# CPU-board-Sheet1-multi-rev_0_1.net
KiCad netlist of a schematic drawn in Altium Designer
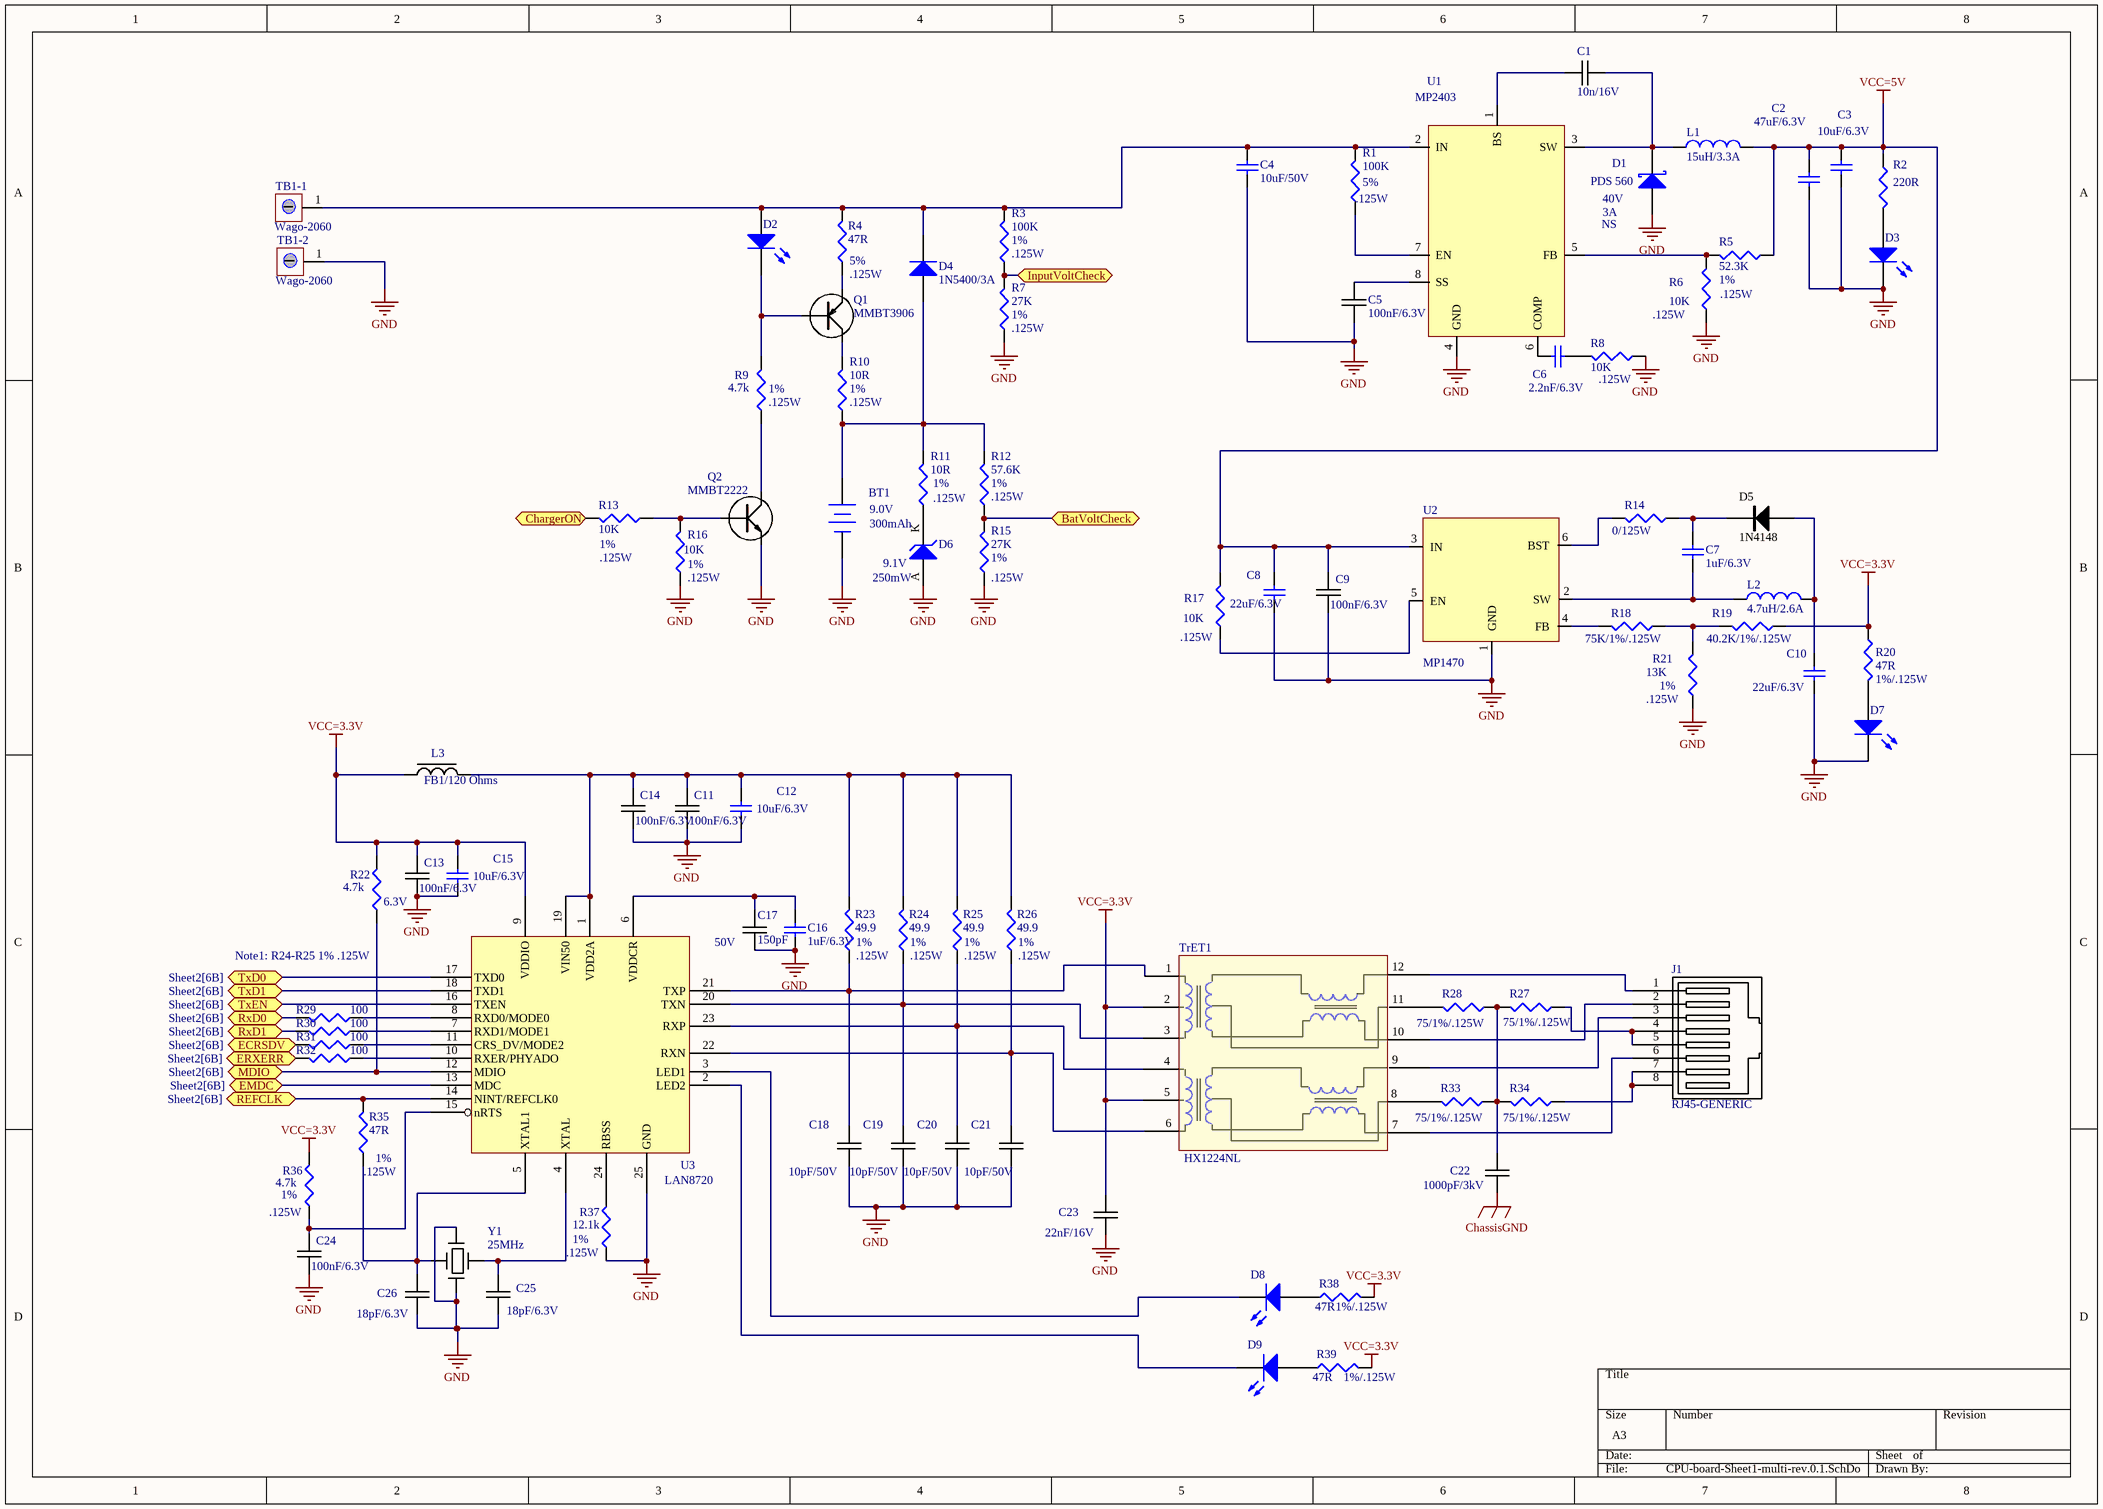
[diagram p0: CPU-board-Sheet1-multi-rev.0.1.SchDoc]

(export (version "E")
  (design (tool "Eeschema 10.0.6"))
  (components
    (comp (ref "BT1")
      (value "9.0V")
      (footprint "BAT-2")
      (description "Multicell Battery")
      (fields
        (field (name "MANUFACTURER") "Guangdong, China (Mainland)")
        (field (name "PUBLISHER") "sunbangpower.en.alibaba.com")
      )
      (libsource (lib "Miscellaneous Devices") (part "Battery"))
    )
    (comp (ref "C1")
      (value "10n/16V")
      (footprint "0402C-GENERIC")
      (description "CAPACITOR 0805 CERAMIC")
      (fields (field (name "MANUFACTURER") "Murata Electronics"))
      (libsource (lib "vh_altium_library") (part "0805C-18PF-50V-C0G-JOH"))
    )
    (comp (ref "C2")
      (value "47uF/6.3V")
      (footprint "1210C-GENERIC")
      (description "Capacitor")
      (fields (field (name "MANUFACTURER") "Murata") (field (name "PUBLISHER") "Altium Limited"))
      (libsource (lib "Miscellaneous Devices") (part "Cap"))
    )
    (comp (ref "C3")
      (value "10uF/6.3V")
      (footprint "0402C-GENERIC")
      (description "Capacitor")
      (fields (field (name "MANUFACTURER") "Murata") (field (name "PUBLISHER") "Altium Limited"))
      (libsource (lib "Miscellaneous Devices") (part "Cap"))
    )
    (comp (ref "C4")
      (value "10uF/50V")
      (footprint "1206C-GENERIC")
      (description "Capacitor")
      (fields (field (name "MANUFACTURER") "Murata") (field (name "PUBLISHER") "Altium Limited"))
      (libsource (lib "Miscellaneous Devices") (part "Cap"))
    )
    (comp (ref "C5")
      (value "100nF/6.3V")
      (footprint "0402C-GENERIC")
      (description "CAPACITOR 0805 CERAMIC")
      (fields (field (name "MANUFACTURER") "Taiyo Yuden"))
      (libsource (lib "vh_altium_library") (part "0805C-18PF-50V-C0G-JOH"))
    )
    (comp (ref "C6")
      (value "2.2nF/6.3V")
      (footprint "0402C-GENERIC")
      (description "Capacitor")
      (fields (field (name "MANUFACTURER") "Murata") (field (name "PUBLISHER") "Altium Limited"))
      (libsource (lib "Miscellaneous Devices") (part "Cap"))
    )
    (comp (ref "C7")
      (value "1uF/6.3V")
      (footprint "0402C-GENERIC")
      (description "Capacitor")
      (fields (field (name "MANUFACTURER") "Murata") (field (name "PUBLISHER") "Altium Limited"))
      (libsource (lib "Miscellaneous Devices") (part "Cap"))
    )
    (comp (ref "C8")
      (value "22uF/6.3V")
      (footprint "1206C-GENERIC")
      (description "Capacitor")
      (fields (field (name "MANUFACTURER") "Murata") (field (name "PUBLISHER") "Altium Limited"))
      (libsource (lib "Miscellaneous Devices") (part "Cap"))
    )
    (comp (ref "C9")
      (value "100nF/6.3V")
      (footprint "0402C-GENERIC")
      (description "CAPACITOR 0805 CERAMIC")
      (fields (field (name "MANUFACTURER") "Taiyo Yuden"))
      (libsource (lib "vh_altium_library") (part "0805C-18PF-50V-C0G-JOH"))
    )
    (comp (ref "C10")
      (value "22uF/6.3V")
      (footprint "1206C-GENERIC")
      (description "Capacitor")
      (fields (field (name "MANUFACTURER") "Murata") (field (name "PUBLISHER") "Altium Limited"))
      (libsource (lib "Miscellaneous Devices") (part "Cap"))
    )
    (comp (ref "C11")
      (value "100nF/6.3V")
      (footprint "0402C-GENERIC")
      (description "CAPACITOR 0805 CERAMIC")
      (fields (field (name "MANUFACTURER") "Taiyo Yuden"))
      (libsource (lib "vh_altium_library") (part "0805C-18PF-50V-C0G-JOH"))
    )
    (comp (ref "C12")
      (value "10uF/6.3V")
      (footprint "0402C-GENERIC")
      (description "Capacitor")
      (fields (field (name "MANUFACTURER") "Murata") (field (name "PUBLISHER") "Altium Limited"))
      (libsource (lib "Miscellaneous Devices") (part "Cap"))
    )
    (comp (ref "C13")
      (value "100nF/6.3V")
      (footprint "0402C-GENERIC")
      (description "CAPACITOR 0805 CERAMIC")
      (fields (field (name "MANUFACTURER") "Taiyo Yuden"))
      (libsource (lib "vh_altium_library") (part "0805C-18PF-50V-C0G-JOH"))
    )
    (comp (ref "C14")
      (value "100nF/6.3V")
      (footprint "0402C-GENERIC")
      (description "CAPACITOR 0805 CERAMIC")
      (fields (field (name "MANUFACTURER") "Taiyo Yuden"))
      (libsource (lib "vh_altium_library") (part "0805C-18PF-50V-C0G-JOH"))
    )
    (comp (ref "C15")
      (value "10uF/6.3V")
      (footprint "0402C-GENERIC")
      (description "Capacitor")
      (fields (field (name "MANUFACTURER") "Murata") (field (name "PUBLISHER") "Altium Limited"))
      (libsource (lib "Miscellaneous Devices") (part "Cap"))
    )
    (comp (ref "C16")
      (value "1uF/6.3V")
      (footprint "0402C-GENERIC")
      (description "Capacitor")
      (fields (field (name "MANUFACTURER") "Murata") (field (name "PUBLISHER") "Altium Limited"))
      (libsource (lib "Miscellaneous Devices") (part "Cap"))
    )
    (comp (ref "C17")
      (value "150pF")
      (footprint "0402C-GENERIC")
      (description "CAPACITOR 0805 CERAMIC")
      (fields (field (name "MANUFACTURER") "Wurth Electronics"))
      (libsource (lib "vh_altium_library") (part "0805C-18PF-50V-C0G-JOH"))
    )
    (comp (ref "C18")
      (value "10pF/50V")
      (footprint "0402C-GENERIC")
      (description "CAPACITOR 0805 CERAMIC")
      (fields (field (name "MANUFACTURER") "Murata"))
      (libsource (lib "vh_altium_library") (part "0805C-18PF-50V-C0G-JOH"))
    )
    (comp (ref "C19")
      (value "10pF/50V")
      (footprint "0402C-GENERIC")
      (description "CAPACITOR 0805 CERAMIC")
      (fields (field (name "MANUFACTURER") "Murata"))
      (libsource (lib "vh_altium_library") (part "0805C-18PF-50V-C0G-JOH"))
    )
    (comp (ref "C20")
      (value "10pF/50V")
      (footprint "0402C-GENERIC")
      (description "CAPACITOR 0805 CERAMIC")
      (fields (field (name "MANUFACTURER") "Murata"))
      (libsource (lib "vh_altium_library") (part "0805C-18PF-50V-C0G-JOH"))
    )
    (comp (ref "C21")
      (value "10pF/50V")
      (footprint "0402C-GENERIC")
      (description "CAPACITOR 0805 CERAMIC")
      (fields (field (name "MANUFACTURER") "Murata"))
      (libsource (lib "vh_altium_library") (part "0805C-18PF-50V-C0G-JOH"))
    )
    (comp (ref "C22")
      (value "1000pF/3kV")
      (footprint "1808")
      (description "CAPACITOR 1808CERAMIC")
      (fields (field (name "MANUFACTURER") "Johanson Dielctrics Inc"))
      (libsource (lib "vh_altium_library") (part "0805C-18PF-50V-C0G-JOH"))
    )
    (comp (ref "C23")
      (value "22nF/16V")
      (footprint "0402C-GENERIC")
      (description "CAPACITOR 0805 CERAMIC")
      (fields (field (name "MANUFACTURER") "Murata Electronics"))
      (libsource (lib "vh_altium_library") (part "0805C-18PF-50V-C0G-JOH"))
    )
    (comp (ref "C24")
      (value "100nF/6.3V")
      (footprint "0402C-GENERIC")
      (description "CAPACITOR 0805 CERAMIC")
      (fields (field (name "MANUFACTURER") "Taiyo Yuden"))
      (libsource (lib "vh_altium_library") (part "0805C-18PF-50V-C0G-JOH"))
    )
    (comp (ref "C25")
      (value "18pF/6.3V")
      (footprint "0402C-GENERIC")
      (description "CAPACITOR 0805 CERAMIC")
      (fields (field (name "MANUFACTURER") "Murata"))
      (libsource (lib "vh_altium_library") (part "0805C-18PF-50V-C0G-JOH"))
    )
    (comp (ref "C26")
      (value "18pF/6.3V")
      (footprint "0402C-GENERIC")
      (description "CAPACITOR 0805 CERAMIC")
      (fields (field (name "MANUFACTURER") "Murata"))
      (libsource (lib "vh_altium_library") (part "0805C-18PF-50V-C0G-JOH"))
    )
    (comp (ref "D1")
      (value "PDS 560")
      (footprint "SMB")
      (description "Schottky Diode")
      (fields (field (name "MANUFACTURER") "Diodes Incorporated") (field (name "PUBLISHER") "Altium Limited"))
      (libsource (lib "Miscellaneous Devices") (part "D Schottky"))
    )
    (comp (ref "D2")
      (value "LED2")
      (footprint "LED-SM")
      (description "Typical RED, GREEN, YELLOW, AMBER GaAs LED")
      (fields (field (name "MANUFACTURER") "Lite-On Inc") (field (name "PUBLISHER") "Altium Limited"))
      (libsource (lib "Miscellaneous Devices") (part "LED2"))
    )
    (comp (ref "D3")
      (value "LED2")
      (footprint "LED-SM")
      (description "Typical RED, GREEN, YELLOW, AMBER GaAs LED")
      (fields (field (name "MANUFACTURER") "Lite-On Inc") (field (name "PUBLISHER") "Altium Limited"))
      (libsource (lib "Miscellaneous Devices") (part "LED2"))
    )
    (comp (ref "D4")
      (value "1N5400/3A")
      (footprint "DO-41")
      (description "1 Amp General Purpose Rectifier")
      (fields (field (name "MANUFACTURER") "NTE Electronics") (field (name "PUBLISHER") "Altium Limited"))
      (libsource (lib "Miscellaneous Devices") (part "Diode 1N4007"))
    )
    (comp (ref "D5")
      (value "1N4148")
      (footprint "SOD-123")
      (description "1N4001")
      (fields (field (name "MANUFACTURER") "Vishay"))
      (libsource (lib "vh_altium_library") (part "1N4001"))
    )
    (comp (ref "D6")
      (value "9.1V")
      (footprint "SOT23-DIODE")
      (description "Zener Diode")
      (fields (field (name "MANUFACTURER") "NXP Semi") (field (name "PUBLISHER") "Altium Limited"))
      (libsource (lib "Miscellaneous Devices") (part "D Zener"))
    )
    (comp (ref "D7")
      (value "LED2")
      (footprint "LED-SM")
      (description "Typical RED, GREEN, YELLOW, AMBER GaAs LED")
      (fields (field (name "MANUFACTURER") "Lite-On Inc") (field (name "PUBLISHER") "Altium Limited"))
      (libsource (lib "Miscellaneous Devices") (part "LED2"))
    )
    (comp (ref "D8")
      (value "LED2")
      (footprint "LED-SM")
      (description "Typical RED, GREEN, YELLOW, AMBER GaAs LED")
      (fields (field (name "MANUFACTURER") "Lite-On Inc") (field (name "PUBLISHER") "Altium Limited"))
      (libsource (lib "Miscellaneous Devices") (part "LED2"))
    )
    (comp (ref "D9")
      (value "LED2")
      (footprint "LED-SM")
      (description "Typical RED, GREEN, YELLOW, AMBER GaAs LED")
      (fields (field (name "MANUFACTURER") "Lite-On Inc") (field (name "PUBLISHER") "Altium Limited"))
      (libsource (lib "Miscellaneous Devices") (part "LED2"))
    )
    (comp (ref "J1")
      (value "RJ45-GENERIC")
      (footprint "RJ45-8/8")
      (description "GENERIC RJ45 CONNECTOR 8 PIN")
      (fields (field (name "MANUFACTURER") "Assman WSW Components"))
      (libsource (lib "vh_altium_library") (part "RJ45-GENERIC"))
    )
    (comp (ref "L1")
      (value "15uH/3.3A")
      (footprint "Murata 15uH inductor")
      (description "Inductor")
      (fields (field (name "MANUFACTURER") "Murata") (field (name "PUBLISHER") "Altium Limited"))
      (libsource (lib "Miscellaneous Devices") (part "Inductor"))
    )
    (comp (ref "L2")
      (value "4.7uH/2.6A")
      (footprint "Inductor 4.7/6.8")
      (description "Inductor")
      (fields (field (name "MANUFACTURER") "Bourns") (field (name "PUBLISHER") "Altium Limited"))
      (libsource (lib "Miscellaneous Devices") (part "Inductor"))
    )
    (comp (ref "L3")
      (value "FB1/120 Ohms")
      (footprint "0603C-2U2")
      (description "1239AS-H-1R0N")
      (fields (field (name "MANUFACTURER") "Murata Electronics"))
      (libsource (lib "SMD Magnetics-SM") (part "1U-1239AS-TOKO"))
    )
    (comp (ref "Q1")
      (value "MMBT3906")
      (footprint "SOT23-BCE")
      (description "GENERIC PNP BIPOLAR TRANSISTOR")
      (fields (field (name "MANUFACTURER") "On Semi"))
      (libsource (lib "generic") (part "PNP-GENERIC"))
    )
    (comp (ref "Q2")
      (value "MMBT2222")
      (footprint "MMBT2222")
      (description "BC847 SMALL SIGNAL NPN TRANSISTOR")
      (fields (field (name "MANUFACTURER") "Diodes  Inc."))
      (libsource (lib "vh_altium_library") (part "MMBT2222"))
    )
    (comp (ref "R1")
      (value "100K")
      (footprint "0402R-TBD")
      (description "Resistor")
      (fields (field (name "MANUFACTURER") "Panasonic") (field (name "PUBLISHER") "Altium Limited"))
      (libsource (lib "Miscellaneous Devices") (part "Res3"))
    )
    (comp (ref "R2")
      (value "220R")
      (footprint "0402R-TBD")
      (description "Resistor")
      (fields (field (name "MANUFACTURER") "Panasonic") (field (name "PUBLISHER") "Altium Limited"))
      (libsource (lib "Miscellaneous Devices") (part "Res3"))
    )
    (comp (ref "R3")
      (value "100K")
      (footprint "0402R-TBD")
      (description "Resistor")
      (fields (field (name "MANUFACTURER") "Panasonic") (field (name "PUBLISHER") "Altium Limited"))
      (libsource (lib "Miscellaneous Devices") (part "Res3"))
    )
    (comp (ref "R4")
      (value "47R")
      (footprint "0402R-TBD")
      (description "Resistor")
      (fields (field (name "PUBLISHER") "Altium Limited"))
      (libsource (lib "Miscellaneous Devices") (part "Res3"))
    )
    (comp (ref "R5")
      (value "52.3K")
      (footprint "0402R-TBD")
      (description "Resistor")
      (fields (field (name "MANUFACTURER") "Panasonic") (field (name "PUBLISHER") "Altium Limited"))
      (libsource (lib "Miscellaneous Devices") (part "Res3"))
    )
    (comp (ref "R6")
      (value "10K")
      (footprint "0402R-TBD")
      (description "Resistor")
      (fields (field (name "MANUFACTURER") "Panasonic") (field (name "PUBLISHER") "Altium Limited"))
      (libsource (lib "Miscellaneous Devices") (part "Res3"))
    )
    (comp (ref "R7")
      (value "27K")
      (footprint "0402R-TBD")
      (description "Resistor")
      (fields (field (name "MANUFACTURER") "Panasonic") (field (name "PUBLISHER") "Altium Limited"))
      (libsource (lib "Miscellaneous Devices") (part "Res3"))
    )
    (comp (ref "R8")
      (value "10K")
      (footprint "0402R-TBD")
      (description "Resistor")
      (fields (field (name "MANUFACTURER") "Panasonic") (field (name "PUBLISHER") "Altium Limited"))
      (libsource (lib "Miscellaneous Devices") (part "Res3"))
    )
    (comp (ref "R9")
      (value "4.7k")
      (footprint "0402R-TBD")
      (description "Resistor")
      (fields (field (name "MANUFACTURER") "Panasonic") (field (name "PUBLISHER") "Altium Limited"))
      (libsource (lib "Miscellaneous Devices") (part "Res3"))
    )
    (comp (ref "R10")
      (value "10R")
      (footprint "0402R-TBD")
      (description "Resistor")
      (fields (field (name "MANUFACTURER") "Panasonic") (field (name "PUBLISHER") "Altium Limited"))
      (libsource (lib "Miscellaneous Devices") (part "Res3"))
    )
    (comp (ref "R11")
      (value "10R")
      (footprint "0402R-TBD")
      (description "Resistor")
      (fields (field (name "MANUFACTURER") "Panasonic") (field (name "PUBLISHER") "Altium Limited"))
      (libsource (lib "Miscellaneous Devices") (part "Res3"))
    )
    (comp (ref "R12")
      (value "57.6K")
      (footprint "0402R-TBD")
      (description "Resistor")
      (fields (field (name "MANUFACTURER") "Panasonic") (field (name "PUBLISHER") "Altium Limited"))
      (libsource (lib "Miscellaneous Devices") (part "Res3"))
    )
    (comp (ref "R13")
      (value "10K")
      (footprint "0402R-TBD")
      (description "Resistor")
      (fields (field (name "MANUFACTURER") "Panasonic") (field (name "PUBLISHER") "Altium Limited"))
      (libsource (lib "Miscellaneous Devices") (part "Res3"))
    )
    (comp (ref "R14")
      (value "0/125W")
      (footprint "0402C-GENERIC")
      (description "Resistor")
      (fields (field (name "MANUFACTURER") "Vishay Dale") (field (name "PUBLISHER") "Altium Limited"))
      (libsource (lib "Miscellaneous Devices") (part "Res3"))
    )
    (comp (ref "R15")
      (value "27K")
      (footprint "0402R-TBD")
      (description "Resistor")
      (fields (field (name "MANUFACTURER") "Panasonic") (field (name "PUBLISHER") "Altium Limited"))
      (libsource (lib "Miscellaneous Devices") (part "Res3"))
    )
    (comp (ref "R16")
      (value "10K")
      (footprint "0402R-TBD")
      (description "Resistor")
      (fields (field (name "MANUFACTURER") "Panasonic") (field (name "PUBLISHER") "Altium Limited"))
      (libsource (lib "Miscellaneous Devices") (part "Res3"))
    )
    (comp (ref "R17")
      (value "10K")
      (footprint "0402R-TBD")
      (description "Resistor")
      (fields (field (name "MANUFACTURER") "Panasonic") (field (name "PUBLISHER") "Altium Limited"))
      (libsource (lib "Miscellaneous Devices") (part "Res3"))
    )
    (comp (ref "R18")
      (value "75K/1%/.125W")
      (footprint "0402C-TBD")
      (description "Resistor")
      (fields (field (name "MANUFACTURER") "Panasonic") (field (name "PUBLISHER") "Altium Limited"))
      (libsource (lib "Miscellaneous Devices") (part "Res3"))
    )
    (comp (ref "R19")
      (value "40.2K/1%/.125W")
      (footprint "0402R-TBD")
      (description "Resistor")
      (fields (field (name "MANUFACTURER") "Panasonic") (field (name "PUBLISHER") "Altium Limited"))
      (libsource (lib "Miscellaneous Devices") (part "Res3"))
    )
    (comp (ref "R20")
      (value "47R")
      (footprint "0402R-TBD")
      (description "Resistor")
      (fields (field (name "PUBLISHER") "Altium Limited"))
      (libsource (lib "Miscellaneous Devices") (part "Res3"))
    )
    (comp (ref "R21")
      (value "13K")
      (footprint "0402R-TBD")
      (description "Resistor")
      (fields (field (name "MANUFACTURER") "Panasonic") (field (name "PUBLISHER") "Altium Limited"))
      (libsource (lib "Miscellaneous Devices") (part "Res3"))
    )
    (comp (ref "R22")
      (value "4.7k")
      (footprint "0402R-TBD")
      (description "Resistor")
      (fields (field (name "MANUFACTURER") "Panasonic") (field (name "PUBLISHER") "Altium Limited"))
      (libsource (lib "Miscellaneous Devices") (part "Res3"))
    )
    (comp (ref "R23")
      (value "49.9")
      (footprint "0402R-TBD")
      (description "Resistor")
      (fields (field (name "MANUFACTURER") "Panasonic") (field (name "PUBLISHER") "Altium Limited"))
      (libsource (lib "Miscellaneous Devices") (part "Res3"))
    )
    (comp (ref "R24")
      (value "49.9")
      (footprint "0402R-TBD")
      (description "Resistor")
      (fields (field (name "MANUFACTURER") "Panasonic") (field (name "PUBLISHER") "Altium Limited"))
      (libsource (lib "Miscellaneous Devices") (part "Res3"))
    )
    (comp (ref "R25")
      (value "49.9")
      (footprint "0402R-TBD")
      (description "Resistor")
      (fields (field (name "MANUFACTURER") "Panasonic") (field (name "PUBLISHER") "Altium Limited"))
      (libsource (lib "Miscellaneous Devices") (part "Res3"))
    )
    (comp (ref "R26")
      (value "49.9")
      (footprint "0402R-TBD")
      (description "Resistor")
      (fields (field (name "MANUFACTURER") "Panasonic") (field (name "PUBLISHER") "Altium Limited"))
      (libsource (lib "Miscellaneous Devices") (part "Res3"))
    )
    (comp (ref "R27")
      (value "75/1%/.125W")
      (footprint "0402R-TBD")
      (description "Resistor")
      (fields (field (name "MANUFACTURER") "Panasonic") (field (name "PUBLISHER") "Altium Limited"))
      (libsource (lib "Miscellaneous Devices") (part "Res3"))
    )
    (comp (ref "R28")
      (value "75/1%/.125W")
      (footprint "0402R-TBD")
      (description "Resistor")
      (fields (field (name "MANUFACTURER") "Panasonic") (field (name "PUBLISHER") "Altium Limited"))
      (libsource (lib "Miscellaneous Devices") (part "Res3"))
    )
    (comp (ref "R29")
      (value "100")
      (footprint "0402R-TBD")
      (description "Resistor")
      (fields (field (name "MANUFACTURER") "Panasonic") (field (name "PUBLISHER") "Altium Limited"))
      (libsource (lib "Miscellaneous Devices") (part "Res3"))
    )
    (comp (ref "R30")
      (value "100")
      (footprint "0402R-TBD")
      (description "Resistor")
      (fields (field (name "MANUFACTURER") "Panasonic") (field (name "PUBLISHER") "Altium Limited"))
      (libsource (lib "Miscellaneous Devices") (part "Res3"))
    )
    (comp (ref "R31")
      (value "100")
      (footprint "0402R-TBD")
      (description "Resistor")
      (fields (field (name "MANUFACTURER") "Panasonic") (field (name "PUBLISHER") "Altium Limited"))
      (libsource (lib "Miscellaneous Devices") (part "Res3"))
    )
    (comp (ref "R32")
      (value "100")
      (footprint "0402R-TBD")
      (description "Resistor")
      (fields (field (name "MANUFACTURER") "Panasonic") (field (name "PUBLISHER") "Altium Limited"))
      (libsource (lib "Miscellaneous Devices") (part "Res3"))
    )
    (comp (ref "R33")
      (value "75/1%/.125W")
      (footprint "0402R-TBD")
      (description "Resistor")
      (fields (field (name "MANUFACTURER") "Panasonic") (field (name "PUBLISHER") "Altium Limited"))
      (libsource (lib "Miscellaneous Devices") (part "Res3"))
    )
    (comp (ref "R34")
      (value "75/1%/.125W")
      (footprint "0402R-TBD")
      (description "Resistor")
      (fields (field (name "MANUFACTURER") "Panasonic") (field (name "PUBLISHER") "Altium Limited"))
      (libsource (lib "Miscellaneous Devices") (part "Res3"))
    )
    (comp (ref "R35")
      (value "47R")
      (footprint "0402R-TBD")
      (description "Resistor")
      (fields (field (name "PUBLISHER") "Altium Limited"))
      (libsource (lib "Miscellaneous Devices") (part "Res3"))
    )
    (comp (ref "R36")
      (value "4.7k")
      (footprint "0402R-TBD")
      (description "Resistor")
      (fields (field (name "MANUFACTURER") "Panasonic") (field (name "PUBLISHER") "Altium Limited"))
      (libsource (lib "Miscellaneous Devices") (part "Res3"))
    )
    (comp (ref "R37")
      (value "12.1k")
      (footprint "0402R-TBD")
      (description "Resistor")
      (fields (field (name "MANUFACTURER") "Panasonic") (field (name "PUBLISHER") "Altium Limited"))
      (libsource (lib "Miscellaneous Devices") (part "Res3"))
    )
    (comp (ref "R38")
      (value "47R")
      (footprint "0402R-TBD")
      (description "Resistor")
      (fields (field (name "PUBLISHER") "Altium Limited"))
      (libsource (lib "Miscellaneous Devices") (part "Res3"))
    )
    (comp (ref "R39")
      (value "47R")
      (footprint "0402R-TBD")
      (description "Resistor")
      (fields (field (name "PUBLISHER") "Altium Limited"))
      (libsource (lib "Miscellaneous Devices") (part "Res3"))
    )
    (comp (ref "TB1-1") (value "Wago-2060") (footprint "WagoTB1-1") (libsource (lib "SMLib") (part "TB-2")))
    (comp (ref "TB1-2") (value "Wago-2060") (footprint "WagoTB1-1") (libsource (lib "SMLib") (part "TB-2")))
    (comp (ref "TrET1")
      (value "HX1224NL")
      (footprint "HX1224-NL")
      (libsource (lib "SMLib") (part "hx1224nl"))
    )
    (comp (ref "U1")
      (value "MP2403")
      (footprint "MP2403")
      (fields (field (name "MANUFACTURER") "MPS Inc"))
      (libsource (lib "SMLib") (part "MP2403"))
    )
    (comp (ref "U2")
      (value "MP1470")
      (footprint "MP1470")
      (fields (field (name "MANUFACTURER") "MPS Inc"))
      (libsource (lib "SMLib") (part "MP1470"))
    )
    (comp (ref "U3")
      (value "LAN8720")
      (footprint "Atmel Multimedia:QFN24_4X4_N")
      (fields (field (name "MANUFACTURER") "Microchip"))
      (libsource (lib "SMLib") (part "LAN8720"))
    )
    (comp (ref "Y1")
      (value "25MHz")
      (footprint "CeramicResonator8-16MHZ")
      (description "25MHz CRYSTAL HC49US SHORT BODY")
      (fields (field (name "MANUFACTURER") "KDS DAISHINKU.Corp"))
      (libsource (lib "Crystals") (part "12MC-HC49US-7MM"))
    )
  )
  (nets
    (net (code "1") (name "/BatVoltCheck") (class "Default")
      (node (ref "R12") (pin "1") (pinfunction "1_1") (pintype "passive"))
      (node (ref "R15") (pin "2") (pinfunction "2_2") (pintype "passive"))
    )
    (net (code "2") (name "/ChargerON") (class "Default")
      (node (ref "R13") (pin "2") (pinfunction "2_2") (pintype "passive"))
    )
    (net (code "3") (name "/ECRSDV") (class "Default")
      (node (ref "R31") (pin "2") (pinfunction "2_2") (pintype "passive"))
    )
    (net (code "4") (name "/EMDC") (class "Default")
      (node (ref "U3") (pin "13") (pinfunction "MDC_13") (pintype "passive"))
    )
    (net (code "5") (name "/ERXERR") (class "Default")
      (node (ref "R32") (pin "2") (pinfunction "2_2") (pintype "passive"))
    )
    (net (code "6") (name "/InputVoltCheck") (class "Default")
      (node (ref "R3") (pin "1") (pinfunction "1_1") (pintype "passive"))
      (node (ref "R7") (pin "2") (pinfunction "2_2") (pintype "passive"))
    )
    (net (code "7") (name "/MDIO") (class "Default")
      (node (ref "R22") (pin "1") (pinfunction "1_1") (pintype "passive"))
      (node (ref "U3") (pin "12") (pinfunction "MDIO_12") (pintype "passive"))
    )
    (net (code "8") (name "/REFCLK") (class "Default")
      (node (ref "R35") (pin "2") (pinfunction "2_2") (pintype "passive"))
      (node (ref "U3") (pin "14") (pinfunction "NINT/REFCLK0_14") (pintype "passive"))
    )
    (net (code "9") (name "/RxD0") (class "Default")
      (node (ref "R29") (pin "2") (pinfunction "2_2") (pintype "passive"))
    )
    (net (code "10") (name "/RxD1") (class "Default")
      (node (ref "R30") (pin "2") (pinfunction "2_2") (pintype "passive"))
    )
    (net (code "11") (name "/TxD0") (class "Default")
      (node (ref "U3") (pin "17") (pinfunction "TXD0_17") (pintype "passive"))
    )
    (net (code "12") (name "/TxD1") (class "Default")
      (node (ref "U3") (pin "18") (pinfunction "TXD1_18") (pintype "passive"))
    )
    (net (code "13") (name "/TxEN") (class "Default")
      (node (ref "U3") (pin "16") (pinfunction "TXEN_16") (pintype "passive"))
    )
    (net (code "14") (name "ChassisGND") (class "Default") (node (ref "C22") (pin "2") (pintype "passive")))
    (net (code "15") (name "GND") (class "Default")
      (node (ref "BT1") (pin "2") (pinfunction "-_2") (pintype "passive"))
      (node (ref "C10") (pin "2") (pinfunction "2_2") (pintype "passive"))
      (node (ref "C11") (pin "2") (pintype "passive"))
      (node (ref "C12") (pin "2") (pinfunction "2_2") (pintype "passive"))
      (node (ref "C13") (pin "2") (pintype "passive"))
      (node (ref "C14") (pin "2") (pintype "passive"))
      (node (ref "C15") (pin "2") (pinfunction "2_2") (pintype "passive"))
      (node (ref "C16") (pin "1") (pinfunction "1_1") (pintype "passive"))
      (node (ref "C17") (pin "2") (pintype "passive"))
      (node (ref "C18") (pin "2") (pintype "passive"))
      (node (ref "C19") (pin "2") (pintype "passive"))
      (node (ref "C2") (pin "2") (pinfunction "2_2") (pintype "passive"))
      (node (ref "C20") (pin "2") (pintype "passive"))
      (node (ref "C21") (pin "2") (pintype "passive"))
      (node (ref "C23") (pin "2") (pintype "passive"))
      (node (ref "C24") (pin "2") (pintype "passive"))
      (node (ref "C25") (pin "2") (pintype "passive"))
      (node (ref "C26") (pin "2") (pintype "passive"))
      (node (ref "C3") (pin "2") (pinfunction "2_2") (pintype "passive"))
      (node (ref "C4") (pin "2") (pinfunction "2_2") (pintype "passive"))
      (node (ref "C5") (pin "1") (pintype "passive"))
      (node (ref "C8") (pin "2") (pinfunction "2_2") (pintype "passive"))
      (node (ref "C9") (pin "2") (pintype "passive"))
      (node (ref "D1") (pin "1") (pinfunction "A_1") (pintype "passive"))
      (node (ref "D3") (pin "2") (pinfunction "K_2") (pintype "passive"))
      (node (ref "D6") (pin "A") (pinfunction "A_A") (pintype "passive"))
      (node (ref "D7") (pin "2") (pinfunction "K_2") (pintype "passive"))
      (node (ref "Q2") (pin "E") (pintype "passive"))
      (node (ref "R15") (pin "1") (pinfunction "1_1") (pintype "passive"))
      (node (ref "R16") (pin "1") (pinfunction "1_1") (pintype "passive"))
      (node (ref "R21") (pin "1") (pinfunction "1_1") (pintype "passive"))
      (node (ref "R37") (pin "1") (pinfunction "1_1") (pintype "passive"))
      (node (ref "R6") (pin "1") (pinfunction "1_1") (pintype "passive"))
      (node (ref "R7") (pin "1") (pinfunction "1_1") (pintype "passive"))
      (node (ref "R8") (pin "1") (pinfunction "1_1") (pintype "passive"))
      (node (ref "TB1-2") (pin "1") (pinfunction "1_1") (pintype "passive"))
      (node (ref "U1") (pin "4") (pinfunction "GND_4") (pintype "passive"))
      (node (ref "U2") (pin "1") (pinfunction "GND_1") (pintype "passive"))
      (node (ref "U3") (pin "25") (pinfunction "GND_25") (pintype "passive"))
      (node (ref "Y1") (pin "2") (pintype "passive"))
      (node (ref "Y1") (pin "4") (pintype "passive"))
    )
    (net (code "16") (name "Net-(BT1-+)") (class "Default")
      (node (ref "BT1") (pin "1") (pinfunction "+_1") (pintype "passive"))
      (node (ref "D4") (pin "1") (pinfunction "A_1") (pintype "passive"))
      (node (ref "R10") (pin "1") (pinfunction "1_1") (pintype "passive"))
      (node (ref "R11") (pin "2") (pinfunction "2_2") (pintype "passive"))
      (node (ref "R12") (pin "2") (pinfunction "2_2") (pintype "passive"))
    )
    (net (code "17") (name "Net-(C6-Pad2)") (class "Default")
      (node (ref "C6") (pin "2") (pinfunction "2_2") (pintype "passive"))
      (node (ref "R8") (pin "2") (pinfunction "2_2") (pintype "passive"))
    )
    (net (code "18") (name "Net-(C7-Pad2)") (class "Default")
      (node (ref "C7") (pin "2") (pinfunction "2_2") (pintype "passive"))
      (node (ref "D5") (pin "K") (pinfunction "K_K") (pintype "passive"))
      (node (ref "R14") (pin "1") (pinfunction "1_1") (pintype "passive"))
    )
    (net (code "19") (name "Net-(C10-Pad1)") (class "Default")
      (node (ref "C10") (pin "1") (pinfunction "1_1") (pintype "passive"))
      (node (ref "D5") (pin "A") (pinfunction "A_A") (pintype "passive"))
      (node (ref "L2") (pin "2") (pinfunction "2_2") (pintype "passive"))
    )
    (net (code "20") (name "Net-(C22-Pad1)") (class "Default")
      (node (ref "C22") (pin "1") (pintype "passive"))
      (node (ref "R27") (pin "2") (pinfunction "2_2") (pintype "passive"))
      (node (ref "R28") (pin "1") (pinfunction "1_1") (pintype "passive"))
      (node (ref "R33") (pin "1") (pinfunction "1_1") (pintype "passive"))
      (node (ref "R34") (pin "2") (pinfunction "2_2") (pintype "passive"))
    )
    (net (code "21") (name "Net-(D1-K)") (class "Default")
      (node (ref "C1") (pin "1") (pintype "passive"))
      (node (ref "D1") (pin "2") (pinfunction "K_2") (pintype "passive"))
      (node (ref "L1") (pin "1") (pinfunction "1_1") (pintype "passive"))
      (node (ref "U1") (pin "3") (pinfunction "SW_3") (pintype "passive"))
    )
    (net (code "22") (name "Net-(D2-A)") (class "Default")
      (node (ref "C4") (pin "1") (pinfunction "1_1") (pintype "passive"))
      (node (ref "D2") (pin "1") (pinfunction "A_1") (pintype "passive"))
      (node (ref "D4") (pin "2") (pinfunction "K_2") (pintype "passive"))
      (node (ref "R1") (pin "2") (pinfunction "2_2") (pintype "passive"))
      (node (ref "R3") (pin "2") (pinfunction "2_2") (pintype "passive"))
      (node (ref "R4") (pin "2") (pinfunction "2_2") (pintype "passive"))
      (node (ref "TB1-1") (pin "1") (pinfunction "1_1") (pintype "passive"))
      (node (ref "U1") (pin "2") (pinfunction "IN_2") (pintype "passive"))
    )
    (net (code "23") (name "Net-(D2-K)") (class "Default")
      (node (ref "D2") (pin "2") (pinfunction "K_2") (pintype "passive"))
      (node (ref "Q1") (pin "B") (pintype "passive"))
      (node (ref "R9") (pin "2") (pinfunction "2_2") (pintype "passive"))
    )
    (net (code "24") (name "Net-(D3-A)") (class "Default")
      (node (ref "D3") (pin "1") (pinfunction "A_1") (pintype "passive"))
      (node (ref "R2") (pin "2") (pinfunction "2_2") (pintype "passive"))
    )
    (net (code "25") (name "Net-(D6-PadK)") (class "Default")
      (node (ref "D6") (pin "K") (pinfunction "K_K") (pintype "passive"))
      (node (ref "R11") (pin "1") (pinfunction "1_1") (pintype "passive"))
    )
    (net (code "26") (name "Net-(D7-A)") (class "Default")
      (node (ref "D7") (pin "1") (pinfunction "A_1") (pintype "passive"))
      (node (ref "R20") (pin "2") (pinfunction "2_2") (pintype "passive"))
    )
    (net (code "27") (name "Net-(D8-A)") (class "Default")
      (node (ref "D8") (pin "1") (pinfunction "A_1") (pintype "passive"))
      (node (ref "R38") (pin "1") (pinfunction "1_1") (pintype "passive"))
    )
    (net (code "28") (name "Net-(D8-K)") (class "Default")
      (node (ref "D8") (pin "2") (pinfunction "K_2") (pintype "passive"))
      (node (ref "U3") (pin "3") (pinfunction "LED1_3") (pintype "passive"))
    )
    (net (code "29") (name "Net-(D9-A)") (class "Default")
      (node (ref "D9") (pin "1") (pinfunction "A_1") (pintype "passive"))
      (node (ref "R39") (pin "1") (pinfunction "1_1") (pintype "passive"))
    )
    (net (code "30") (name "Net-(D9-K)") (class "Default")
      (node (ref "D9") (pin "2") (pinfunction "K_2") (pintype "passive"))
      (node (ref "U3") (pin "2") (pinfunction "LED2_2") (pintype "passive"))
    )
    (net (code "31") (name "Net-(J1-Pad1)") (class "Default")
      (node (ref "J1") (pin "1") (pintype "passive"))
      (node (ref "TrET1") (pin "12") (pinfunction "12_12") (pintype "passive"))
    )
    (net (code "32") (name "Net-(J1-Pad2)") (class "Default")
      (node (ref "J1") (pin "2") (pintype "passive"))
      (node (ref "TrET1") (pin "10") (pinfunction "10_10") (pintype "passive"))
    )
    (net (code "33") (name "Net-(J1-Pad3)") (class "Default")
      (node (ref "J1") (pin "3") (pintype "passive"))
      (node (ref "TrET1") (pin "9") (pinfunction "9_9") (pintype "passive"))
    )
    (net (code "34") (name "Net-(J1-Pad4)") (class "Default")
      (node (ref "J1") (pin "4") (pintype "passive"))
      (node (ref "J1") (pin "5") (pintype "passive"))
      (node (ref "R27") (pin "1") (pinfunction "1_1") (pintype "passive"))
    )
    (net (code "35") (name "Net-(J1-Pad6)") (class "Default")
      (node (ref "J1") (pin "6") (pintype "passive"))
      (node (ref "TrET1") (pin "7") (pinfunction "7_7") (pintype "passive"))
    )
    (net (code "36") (name "Net-(J1-Pad7)") (class "Default")
      (node (ref "J1") (pin "7") (pintype "passive"))
      (node (ref "J1") (pin "8") (pintype "passive"))
      (node (ref "R34") (pin "1") (pinfunction "1_1") (pintype "passive"))
    )
    (net (code "37") (name "Net-(Q1-PadC)") (class "Default")
      (node (ref "Q1") (pin "C") (pintype "passive"))
      (node (ref "R10") (pin "2") (pinfunction "2_2") (pintype "passive"))
    )
    (net (code "38") (name "Net-(Q1-PadE)") (class "Default")
      (node (ref "Q1") (pin "E") (pintype "passive"))
      (node (ref "R4") (pin "1") (pinfunction "1_1") (pintype "passive"))
    )
    (net (code "39") (name "Net-(Q2-PadB)") (class "Default")
      (node (ref "Q2") (pin "B") (pintype "passive"))
      (node (ref "R13") (pin "1") (pinfunction "1_1") (pintype "passive"))
      (node (ref "R16") (pin "2") (pinfunction "2_2") (pintype "passive"))
    )
    (net (code "40") (name "Net-(Q2-PadC)") (class "Default")
      (node (ref "Q2") (pin "C") (pintype "passive"))
      (node (ref "R9") (pin "1") (pinfunction "1_1") (pintype "passive"))
    )
    (net (code "41") (name "Net-(R18-Pad1)") (class "Default")
      (node (ref "R18") (pin "1") (pinfunction "1_1") (pintype "passive"))
      (node (ref "R19") (pin "2") (pinfunction "2_2") (pintype "passive"))
      (node (ref "R21") (pin "2") (pinfunction "2_2") (pintype "passive"))
    )
    (net (code "42") (name "Net-(R28-Pad2)") (class "Default")
      (node (ref "R28") (pin "2") (pinfunction "2_2") (pintype "passive"))
      (node (ref "TrET1") (pin "11") (pinfunction "11_11") (pintype "passive"))
    )
    (net (code "43") (name "Net-(R33-Pad2)") (class "Default")
      (node (ref "R33") (pin "2") (pinfunction "2_2") (pintype "passive"))
      (node (ref "TrET1") (pin "8") (pinfunction "8_8") (pintype "passive"))
    )
    (net (code "44") (name "Net-(TrET1-TD+)") (class "Default")
      (node (ref "C18") (pin "1") (pintype "passive"))
      (node (ref "R23") (pin "1") (pinfunction "1_1") (pintype "passive"))
      (node (ref "TrET1") (pin "1") (pinfunction "TD+_1") (pintype "passive"))
      (node (ref "U3") (pin "21") (pinfunction "TXP_21") (pintype "passive"))
    )
    (net (code "45") (name "Net-(TrET1-TD-)") (class "Default")
      (node (ref "C19") (pin "1") (pintype "passive"))
      (node (ref "R24") (pin "1") (pinfunction "1_1") (pintype "passive"))
      (node (ref "TrET1") (pin "3") (pinfunction "TD-_3") (pintype "passive"))
      (node (ref "U3") (pin "20") (pinfunction "TXN_20") (pintype "passive"))
    )
    (net (code "46") (name "Net-(U1-BS)") (class "Default")
      (node (ref "C1") (pin "2") (pintype "passive"))
      (node (ref "U1") (pin "1") (pinfunction "BS_1") (pintype "passive"))
    )
    (net (code "47") (name "Net-(U1-COMP)") (class "Default")
      (node (ref "C6") (pin "1") (pinfunction "1_1") (pintype "passive"))
      (node (ref "U1") (pin "6") (pinfunction "COMP_6") (pintype "passive"))
    )
    (net (code "48") (name "Net-(U1-EN)") (class "Default")
      (node (ref "R1") (pin "1") (pinfunction "1_1") (pintype "passive"))
      (node (ref "U1") (pin "7") (pinfunction "EN_7") (pintype "passive"))
    )
    (net (code "49") (name "Net-(U1-FB)") (class "Default")
      (node (ref "R5") (pin "2") (pinfunction "2_2") (pintype "passive"))
      (node (ref "R6") (pin "2") (pinfunction "2_2") (pintype "passive"))
      (node (ref "U1") (pin "5") (pinfunction "FB_5") (pintype "passive"))
    )
    (net (code "50") (name "Net-(U1-SS)") (class "Default")
      (node (ref "C5") (pin "2") (pintype "passive"))
      (node (ref "U1") (pin "8") (pinfunction "SS_8") (pintype "passive"))
    )
    (net (code "51") (name "Net-(U2-BST)") (class "Default")
      (node (ref "R14") (pin "2") (pinfunction "2_2") (pintype "passive"))
      (node (ref "U2") (pin "6") (pinfunction "BST_6") (pintype "passive"))
    )
    (net (code "52") (name "Net-(U2-EN)") (class "Default")
      (node (ref "R17") (pin "1") (pinfunction "1_1") (pintype "passive"))
      (node (ref "U2") (pin "5") (pinfunction "EN_5") (pintype "passive"))
    )
    (net (code "53") (name "Net-(U2-FB)") (class "Default")
      (node (ref "R18") (pin "2") (pinfunction "2_2") (pintype "passive"))
      (node (ref "U2") (pin "4") (pinfunction "FB_4") (pintype "passive"))
    )
    (net (code "54") (name "Net-(U2-SW)") (class "Default")
      (node (ref "C7") (pin "1") (pinfunction "1_1") (pintype "passive"))
      (node (ref "L2") (pin "1") (pinfunction "1_1") (pintype "passive"))
      (node (ref "U2") (pin "2") (pinfunction "SW_2") (pintype "passive"))
    )
    (net (code "55") (name "Net-(U3-CRS_DV{slash}MODE2)") (class "Default")
      (node (ref "R31") (pin "1") (pinfunction "1_1") (pintype "passive"))
      (node (ref "U3") (pin "11") (pinfunction "CRS_DV/MODE2_11") (pintype "passive"))
    )
    (net (code "56") (name "Net-(U3-RBSS)") (class "Default")
      (node (ref "R37") (pin "2") (pinfunction "2_2") (pintype "passive"))
      (node (ref "U3") (pin "24") (pinfunction "RBSS_24") (pintype "passive"))
    )
    (net (code "57") (name "Net-(U3-RXD0{slash}MODE0)") (class "Default")
      (node (ref "R29") (pin "1") (pinfunction "1_1") (pintype "passive"))
      (node (ref "U3") (pin "8") (pinfunction "RXD0/MODE0_8") (pintype "passive"))
    )
    (net (code "58") (name "Net-(U3-RXD1{slash}MODE1)") (class "Default")
      (node (ref "R30") (pin "1") (pinfunction "1_1") (pintype "passive"))
      (node (ref "U3") (pin "7") (pinfunction "RXD1/MODE1_7") (pintype "passive"))
    )
    (net (code "59") (name "Net-(U3-RXER{slash}PHYADO)") (class "Default")
      (node (ref "R32") (pin "1") (pinfunction "1_1") (pintype "passive"))
      (node (ref "U3") (pin "10") (pinfunction "RXER/PHYADO_10") (pintype "passive"))
    )
    (net (code "60") (name "Net-(U3-RXN)") (class "Default")
      (node (ref "C21") (pin "1") (pintype "passive"))
      (node (ref "R26") (pin "1") (pinfunction "1_1") (pintype "passive"))
      (node (ref "TrET1") (pin "6") (pinfunction "6_6") (pintype "passive"))
      (node (ref "U3") (pin "22") (pinfunction "RXN_22") (pintype "passive"))
    )
    (net (code "61") (name "Net-(U3-RXP)") (class "Default")
      (node (ref "C20") (pin "1") (pintype "passive"))
      (node (ref "R25") (pin "1") (pinfunction "1_1") (pintype "passive"))
      (node (ref "TrET1") (pin "4") (pinfunction "4_4") (pintype "passive"))
      (node (ref "U3") (pin "23") (pinfunction "RXP_23") (pintype "passive"))
    )
    (net (code "62") (name "Net-(U3-VDD2A)") (class "Default")
      (node (ref "C11") (pin "1") (pintype "passive"))
      (node (ref "C12") (pin "1") (pinfunction "1_1") (pintype "passive"))
      (node (ref "C14") (pin "1") (pintype "passive"))
      (node (ref "L3") (pin "2") (pinfunction "2_2") (pintype "passive"))
      (node (ref "R23") (pin "2") (pinfunction "2_2") (pintype "passive"))
      (node (ref "R24") (pin "2") (pinfunction "2_2") (pintype "passive"))
      (node (ref "R25") (pin "2") (pinfunction "2_2") (pintype "passive"))
      (node (ref "R26") (pin "2") (pinfunction "2_2") (pintype "passive"))
      (node (ref "U3") (pin "1") (pinfunction "VDD2A_1") (pintype "passive"))
      (node (ref "U3") (pin "19") (pinfunction "VIN50_19") (pintype "passive"))
    )
    (net (code "63") (name "Net-(U3-VDDCR)") (class "Default")
      (node (ref "C16") (pin "2") (pinfunction "2_2") (pintype "passive"))
      (node (ref "C17") (pin "1") (pintype "passive"))
      (node (ref "U3") (pin "6") (pinfunction "VDDCR_6") (pintype "passive"))
    )
    (net (code "64") (name "Net-(U3-XTAL)") (class "Default")
      (node (ref "C25") (pin "1") (pintype "passive"))
      (node (ref "U3") (pin "4") (pinfunction "XTAL_4") (pintype "passive"))
      (node (ref "Y1") (pin "1") (pintype "passive"))
    )
    (net (code "65") (name "Net-(U3-XTAL1)") (class "Default")
      (node (ref "C26") (pin "1") (pintype "passive"))
      (node (ref "R35") (pin "1") (pinfunction "1_1") (pintype "passive"))
      (node (ref "U3") (pin "5") (pinfunction "XTAL1_5") (pintype "passive"))
      (node (ref "Y1") (pin "3") (pintype "passive"))
    )
    (net (code "66") (name "Net-(U3-nRTS)") (class "Default")
      (node (ref "C24") (pin "1") (pintype "passive"))
      (node (ref "R36") (pin "1") (pinfunction "1_1") (pintype "passive"))
      (node (ref "U3") (pin "15") (pinfunction "nRTS_15") (pintype "passive"))
    )
    (net (code "67") (name "VCC=3.3V") (class "Default")
      (node (ref "C13") (pin "1") (pintype "passive"))
      (node (ref "C15") (pin "1") (pinfunction "1_1") (pintype "passive"))
      (node (ref "C23") (pin "1") (pintype "passive"))
      (node (ref "L3") (pin "1") (pinfunction "1_1") (pintype "passive"))
      (node (ref "R19") (pin "1") (pinfunction "1_1") (pintype "passive"))
      (node (ref "R20") (pin "1") (pinfunction "1_1") (pintype "passive"))
      (node (ref "R22") (pin "2") (pinfunction "2_2") (pintype "passive"))
      (node (ref "R36") (pin "2") (pinfunction "2_2") (pintype "passive"))
      (node (ref "R38") (pin "2") (pinfunction "2_2") (pintype "passive"))
      (node (ref "R39") (pin "2") (pinfunction "2_2") (pintype "passive"))
      (node (ref "TrET1") (pin "2") (pinfunction "TDCT_2") (pintype "passive"))
      (node (ref "TrET1") (pin "5") (pinfunction "5_5") (pintype "passive"))
      (node (ref "U3") (pin "9") (pinfunction "VDDIO_9") (pintype "passive"))
    )
    (net (code "68") (name "VCC=5V") (class "Default")
      (node (ref "C2") (pin "1") (pinfunction "1_1") (pintype "passive"))
      (node (ref "C3") (pin "1") (pinfunction "1_1") (pintype "passive"))
      (node (ref "C8") (pin "1") (pinfunction "1_1") (pintype "passive"))
      (node (ref "C9") (pin "1") (pintype "passive"))
      (node (ref "L1") (pin "2") (pinfunction "2_2") (pintype "passive"))
      (node (ref "R17") (pin "2") (pinfunction "2_2") (pintype "passive"))
      (node (ref "R2") (pin "1") (pinfunction "1_1") (pintype "passive"))
      (node (ref "R5") (pin "1") (pinfunction "1_1") (pintype "passive"))
      (node (ref "U2") (pin "3") (pinfunction "IN_3") (pintype "passive"))
    )
  )
)
